# arduino_ISCP.net
KiCad netlist of a schematic drawn in EAGLE
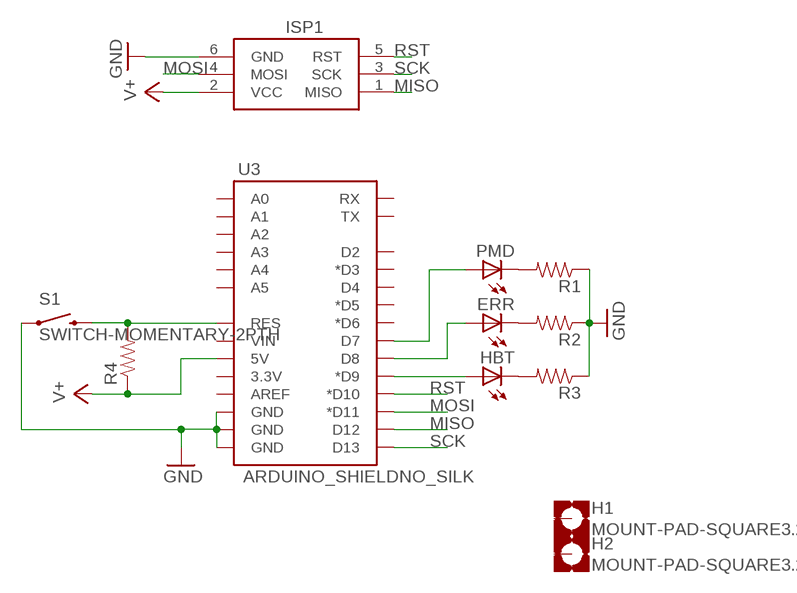
[diagram p0: schematic, sheet 1]

(export (version "E")
  (design (tool "Eeschema 10.0.6"))
  (components
    (comp (ref "ERR")
      (value "LED5MM")
      (footprint "eagle-import:LED5MM")
      (libsource (lib "eagle-import") (part "LED5MM"))
    )
    (comp (ref "H1")
      (value "MOUNT-PAD-SQUARE3.2")
      (footprint "eagle-import:3,2-PAD-SQUARE")
      (libsource (lib "eagle-import") (part "MOUNT-PAD-SQUARE3.2"))
    )
    (comp (ref "H2")
      (value "MOUNT-PAD-SQUARE3.2")
      (footprint "eagle-import:3,2-PAD-SQUARE")
      (libsource (lib "eagle-import") (part "MOUNT-PAD-SQUARE3.2"))
    )
    (comp (ref "HBT")
      (value "LED5MM")
      (footprint "eagle-import:LED5MM")
      (libsource (lib "eagle-import") (part "LED5MM"))
    )
    (comp (ref "ISP1")
      (value "AVRISP-6")
      (footprint "eagle-import:AVRISP")
      (libsource (lib "eagle-import") (part "AVRISP-6"))
    )
    (comp (ref "PMD")
      (value "LED5MM")
      (footprint "eagle-import:LED5MM")
      (libsource (lib "eagle-import") (part "LED5MM"))
    )
    (comp (ref "R1")
      (value "RESISTORPTH-1/4W")
      (footprint "eagle-import:AXIAL-0.4")
      (libsource (lib "eagle-import") (part "RESISTORPTH-1/4W"))
    )
    (comp (ref "R2")
      (value "RESISTORPTH-1/4W")
      (footprint "eagle-import:AXIAL-0.4")
      (libsource (lib "eagle-import") (part "RESISTORPTH-1/4W"))
    )
    (comp (ref "R3")
      (value "RESISTORPTH-1/4W")
      (footprint "eagle-import:AXIAL-0.4")
      (libsource (lib "eagle-import") (part "RESISTORPTH-1/4W"))
    )
    (comp (ref "R4")
      (value "RESISTORPTH-1/4W")
      (footprint "eagle-import:AXIAL-0.4")
      (libsource (lib "eagle-import") (part "RESISTORPTH-1/4W"))
    )
    (comp (ref "S1")
      (value "SWITCH-MOMENTARY-2PTH")
      (footprint "eagle-import:TACTILE-PTH")
      (libsource (lib "eagle-import") (part "SWITCH-MOMENTARY-2PTH"))
    )
    (comp (ref "U3")
      (value "ARDUINO_SHIELDNO_SILK")
      (footprint "eagle-import:DUEMILANOVE_VIAS")
      (libsource (lib "eagle-import") (part "ARDUINO_SHIELDNO_SILK"))
    )
  )
  (nets
    (net (code "1") (name "/MISO") (class "Default")
      (node (ref "ISP1") (pin "1") (pinfunction "MISO_1") (pintype "input"))
      (node (ref "U3") (pin "D12") (pinfunction "D12_D12") (pintype "bidirectional"))
    )
    (net (code "2") (name "/MOSI") (class "Default")
      (node (ref "ISP1") (pin "4") (pinfunction "MOSI_4") (pintype "output"))
      (node (ref "U3") (pin "D11") (pinfunction "*D11_D11") (pintype "bidirectional"))
    )
    (net (code "3") (name "/RST") (class "Default")
      (node (ref "ISP1") (pin "5") (pinfunction "RST_5") (pintype "output"))
      (node (ref "U3") (pin "D10") (pinfunction "*D10_D10") (pintype "bidirectional"))
    )
    (net (code "4") (name "/SCK") (class "Default")
      (node (ref "ISP1") (pin "3") (pinfunction "SCK_3") (pintype "output"))
      (node (ref "U3") (pin "D13") (pinfunction "D13_D13") (pintype "bidirectional"))
    )
    (net (code "5") (name "GND") (class "Default")
      (node (ref "ISP1") (pin "6") (pinfunction "GND_6") (pintype "power_in"))
      (node (ref "R1") (pin "P$1") (pinfunction "1_P$1") (pintype "passive"))
      (node (ref "R2") (pin "P$1") (pinfunction "1_P$1") (pintype "passive"))
      (node (ref "R3") (pin "P$1") (pinfunction "1_P$1") (pintype "passive"))
      (node (ref "S1") (pin "1") (pinfunction "1_1") (pintype "passive"))
      (node (ref "U3") (pin "GND@0") (pinfunction "GND_GND@0") (pintype "bidirectional"))
      (node (ref "U3") (pin "GND@1") (pinfunction "GND_GND@1") (pintype "bidirectional"))
      (node (ref "U3") (pin "GND@2") (pinfunction "GND_GND@2") (pintype "bidirectional"))
    )
    (net (code "6") (name "Net-(ERR-C)") (class "Default")
      (node (ref "ERR") (pin "K") (pinfunction "C_K") (pintype "passive"))
      (node (ref "R2") (pin "P$2") (pinfunction "2_P$2") (pintype "passive"))
    )
    (net (code "7") (name "Net-(ERR-PadA)") (class "Default")
      (node (ref "ERR") (pin "A") (pinfunction "A_A") (pintype "passive"))
      (node (ref "U3") (pin "D8") (pinfunction "D8_D8") (pintype "bidirectional"))
    )
    (net (code "8") (name "Net-(HBT-C)") (class "Default")
      (node (ref "HBT") (pin "K") (pinfunction "C_K") (pintype "passive"))
      (node (ref "R3") (pin "P$2") (pinfunction "2_P$2") (pintype "passive"))
    )
    (net (code "9") (name "Net-(PMD-C)") (class "Default")
      (node (ref "PMD") (pin "K") (pinfunction "C_K") (pintype "passive"))
      (node (ref "R1") (pin "P$2") (pinfunction "2_P$2") (pintype "passive"))
    )
    (net (code "10") (name "Net-(PMD-PadA)") (class "Default")
      (node (ref "PMD") (pin "A") (pinfunction "A_A") (pintype "passive"))
      (node (ref "U3") (pin "D7") (pinfunction "D7_D7") (pintype "bidirectional"))
    )
    (net (code "11") (name "Net-(R4-2)") (class "Default")
      (node (ref "R4") (pin "P$2") (pinfunction "2_P$2") (pintype "passive"))
      (node (ref "S1") (pin "3") (pinfunction "2_3") (pintype "passive"))
      (node (ref "U3") (pin "RES") (pinfunction "RES_RES") (pintype "bidirectional"))
    )
    (net (code "12") (name "Net-(U3-*D9)") (class "Default")
      (node (ref "HBT") (pin "A") (pinfunction "A_A") (pintype "passive"))
      (node (ref "U3") (pin "D9") (pinfunction "*D9_D9") (pintype "bidirectional"))
    )
    (net (code "13") (name "V+") (class "Default")
      (node (ref "ISP1") (pin "2") (pinfunction "VCC_2") (pintype "power_in"))
      (node (ref "R4") (pin "P$1") (pinfunction "1_P$1") (pintype "passive"))
      (node (ref "U3") (pin "5V") (pinfunction "5V_5V") (pintype "bidirectional"))
    )
    (net (code "14") (name "unconnected-(H1-MOUNT-PadB3,2)") (class "Default")
      (node (ref "H1") (pin "B3,2") (pinfunction "MOUNT_B3,2") (pintype "passive"))
    )
    (net (code "15") (name "unconnected-(H2-MOUNT-PadB3,2)") (class "Default")
      (node (ref "H2") (pin "B3,2") (pinfunction "MOUNT_B3,2") (pintype "passive"))
    )
    (net (code "16") (name "unconnected-(U3-*D3-PadD3)") (class "Default")
      (node (ref "U3") (pin "D3") (pinfunction "*D3_D3") (pintype "bidirectional"))
    )
    (net (code "17") (name "unconnected-(U3-*D5-PadD5)") (class "Default")
      (node (ref "U3") (pin "D5") (pinfunction "*D5_D5") (pintype "bidirectional"))
    )
    (net (code "18") (name "unconnected-(U3-*D6-PadD6)") (class "Default")
      (node (ref "U3") (pin "D6") (pinfunction "*D6_D6") (pintype "bidirectional"))
    )
    (net (code "19") (name "unconnected-(U3-Pad3.3V)") (class "Default")
      (node (ref "U3") (pin "3.3V") (pinfunction "3.3V_3.3V") (pintype "bidirectional"))
    )
    (net (code "20") (name "unconnected-(U3-PadA0)") (class "Default")
      (node (ref "U3") (pin "A0") (pinfunction "A0_A0") (pintype "bidirectional"))
    )
    (net (code "21") (name "unconnected-(U3-PadA1)") (class "Default")
      (node (ref "U3") (pin "A1") (pinfunction "A1_A1") (pintype "bidirectional"))
    )
    (net (code "22") (name "unconnected-(U3-PadA2)") (class "Default")
      (node (ref "U3") (pin "A2") (pinfunction "A2_A2") (pintype "bidirectional"))
    )
    (net (code "23") (name "unconnected-(U3-PadA3)") (class "Default")
      (node (ref "U3") (pin "A3") (pinfunction "A3_A3") (pintype "bidirectional"))
    )
    (net (code "24") (name "unconnected-(U3-PadA4)") (class "Default")
      (node (ref "U3") (pin "A4") (pinfunction "A4_A4") (pintype "bidirectional"))
    )
    (net (code "25") (name "unconnected-(U3-PadA5)") (class "Default")
      (node (ref "U3") (pin "A5") (pinfunction "A5_A5") (pintype "bidirectional"))
    )
    (net (code "26") (name "unconnected-(U3-PadAREF)") (class "Default")
      (node (ref "U3") (pin "AREF") (pinfunction "AREF_AREF") (pintype "bidirectional"))
    )
    (net (code "27") (name "unconnected-(U3-PadD2)") (class "Default")
      (node (ref "U3") (pin "D2") (pinfunction "D2_D2") (pintype "bidirectional"))
    )
    (net (code "28") (name "unconnected-(U3-PadD4)") (class "Default")
      (node (ref "U3") (pin "D4") (pinfunction "D4_D4") (pintype "bidirectional"))
    )
    (net (code "29") (name "unconnected-(U3-PadRX)") (class "Default")
      (node (ref "U3") (pin "RX") (pinfunction "RX_RX") (pintype "bidirectional"))
    )
    (net (code "30") (name "unconnected-(U3-PadTX)") (class "Default")
      (node (ref "U3") (pin "TX") (pinfunction "TX_TX") (pintype "bidirectional"))
    )
    (net (code "31") (name "unconnected-(U3-PadVIN)") (class "Default")
      (node (ref "U3") (pin "VIN") (pinfunction "VIN_VIN") (pintype "bidirectional"))
    )
  )
)
